# LCD_boad.net
KiCad netlist of a schematic drawn in EAGLE
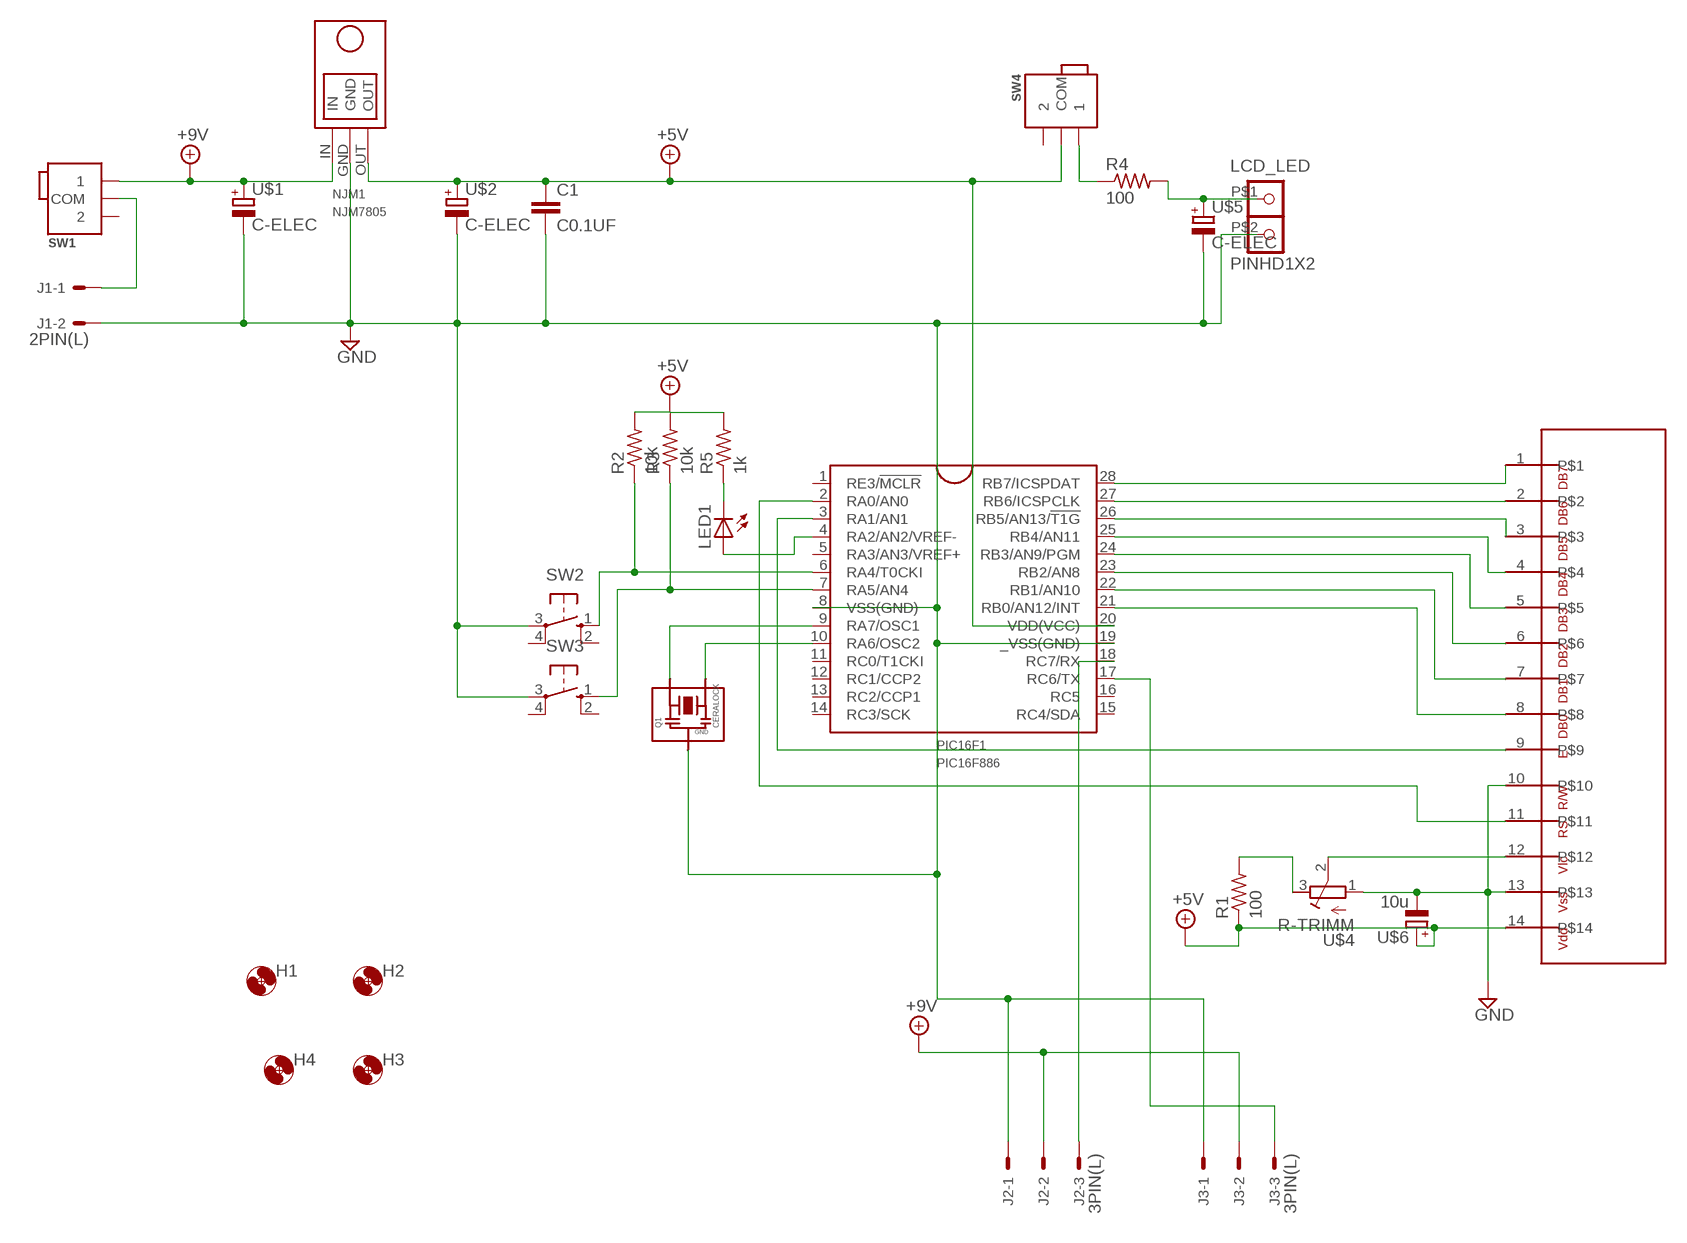
[diagram p0: schematic, sheet 1]

(export (version "E")
  (design (tool "Eeschema 10.0.6"))
  (components
    (comp (ref "C1")
      (value "C0.1UF")
      (footprint "eagle-import:C0.1UF")
      (libsource (lib "eagle-import") (part "C0.1UF"))
    )
    (comp (ref "H1")
      (value "HOLE3.3M3BOLT")
      (footprint "eagle-import:HOLE3.3")
      (libsource (lib "eagle-import") (part "HOLE3.3M3BOLT"))
    )
    (comp (ref "H2")
      (value "HOLE3.3M3BOLT")
      (footprint "eagle-import:HOLE3.3")
      (libsource (lib "eagle-import") (part "HOLE3.3M3BOLT"))
    )
    (comp (ref "H3")
      (value "HOLE3.3M3BOLT")
      (footprint "eagle-import:HOLE3.3")
      (libsource (lib "eagle-import") (part "HOLE3.3M3BOLT"))
    )
    (comp (ref "H4")
      (value "HOLE3.3M3BOLT")
      (footprint "eagle-import:HOLE3.3")
      (libsource (lib "eagle-import") (part "HOLE3.3M3BOLT"))
    )
    (comp (ref "J1")
      (value "2PIN(L)")
      (footprint "eagle-import:2PL")
      (libsource (lib "eagle-import") (part "2PIN(L)"))
    )
    (comp (ref "J2")
      (value "3PIN(L)")
      (footprint "eagle-import:3PL")
      (libsource (lib "eagle-import") (part "3PIN(L)"))
    )
    (comp (ref "J3")
      (value "3PIN(L)")
      (footprint "eagle-import:3PL")
      (libsource (lib "eagle-import") (part "3PIN(L)"))
    )
    (comp (ref "LCD_LED")
      (value "PINHD1X2")
      (footprint "eagle-import:PINHD1X2")
      (libsource (lib "eagle-import") (part "PINHD1X2"))
    )
    (comp (ref "LED1")
      (value "LED")
      (footprint "eagle-import:LED5MM")
      (libsource (lib "eagle-import") (part "LED"))
    )
    (comp (ref "NJM1")
      (value "NJM7805")
      (footprint "eagle-import:NJM7805")
      (libsource (lib "eagle-import") (part "NJM7805"))
    )
    (comp (ref "PIC16F1")
      (value "PIC16F886")
      (footprint "eagle-import:DIL28-3")
      (libsource (lib "eagle-import") (part "PIC16F886"))
    )
    (comp (ref "Q1")
      (value "CERALOCK")
      (footprint "eagle-import:CERALOCK")
      (libsource (lib "eagle-import") (part "CERALOCK"))
    )
    (comp (ref "R1")
      (value "100")
      (footprint "eagle-import:0207_10")
      (libsource (lib "eagle-import") (part "R-"))
    )
    (comp (ref "R2")
      (value "10k")
      (footprint "eagle-import:0207_10")
      (libsource (lib "eagle-import") (part "R-"))
    )
    (comp (ref "R3")
      (value "10k")
      (footprint "eagle-import:0207_10")
      (libsource (lib "eagle-import") (part "R-"))
    )
    (comp (ref "R4")
      (value "100")
      (footprint "eagle-import:0207_10")
      (libsource (lib "eagle-import") (part "R-"))
    )
    (comp (ref "R5")
      (value "1k")
      (footprint "eagle-import:0207_10")
      (libsource (lib "eagle-import") (part "R-"))
    )
    (comp (ref "SW1")
      (value "SWITCH_MININORMAL")
      (footprint "eagle-import:SWITCH_MINI")
      (libsource (lib "eagle-import") (part "SWITCH_MININORMAL"))
    )
    (comp (ref "SW2")
      (value "TACTSW")
      (footprint "eagle-import:TACT")
      (libsource (lib "eagle-import") (part "TACTSW"))
    )
    (comp (ref "SW3")
      (value "TACTSW")
      (footprint "eagle-import:TACT")
      (libsource (lib "eagle-import") (part "TACTSW"))
    )
    (comp (ref "SW4")
      (value "SWITCH_MININORMAL")
      (footprint "eagle-import:SWITCH_MINI")
      (libsource (lib "eagle-import") (part "SWITCH_MININORMAL"))
    )
    (comp (ref "U$1")
      (value "C-ELEC")
      (footprint "eagle-import:C-6MM")
      (libsource (lib "eagle-import") (part "C-ELEC"))
    )
    (comp (ref "U$2")
      (value "C-ELEC")
      (footprint "eagle-import:C-6MM")
      (libsource (lib "eagle-import") (part "C-ELEC"))
    )
    (comp (ref "U$3")
      (value "L1672D1JOOO")
      (footprint "eagle-import:Ｌ１６７２Ｄ１Ｊ０００")
      (libsource (lib "eagle-import") (part "L1672D1JOOO"))
    )
    (comp (ref "U$4")
      (value "R-TRIMM")
      (footprint "eagle-import:R-TRIMM")
      (libsource (lib "eagle-import") (part "R-TRIMM"))
    )
    (comp (ref "U$5")
      (value "C-ELEC")
      (footprint "eagle-import:C-6MM")
      (libsource (lib "eagle-import") (part "C-ELEC"))
    )
    (comp (ref "U$6")
      (value "10u")
      (footprint "eagle-import:C-6MM")
      (libsource (lib "eagle-import") (part "C-ELEC"))
    )
  )
  (nets
    (net (code "1") (name "+5V") (class "Default")
      (node (ref "C1") (pin "1") (pinfunction "1_1") (pintype "passive"))
      (node (ref "NJM1") (pin "OUT") (pinfunction "OUT_OUT") (pintype "bidirectional"))
      (node (ref "PIC16F1") (pin "20") (pinfunction "VDD(VCC)_20") (pintype "power_in"))
      (node (ref "R1") (pin "1") (pinfunction "1_1") (pintype "passive"))
      (node (ref "R2") (pin "2") (pinfunction "2_2") (pintype "passive"))
      (node (ref "R3") (pin "2") (pinfunction "2_2") (pintype "passive"))
      (node (ref "R5") (pin "2") (pinfunction "2_2") (pintype "passive"))
      (node (ref "SW4") (pin "COM") (pinfunction "COM_COM") (pintype "passive"))
      (node (ref "U$2") (pin "+") (pinfunction "+_+") (pintype "passive"))
      (node (ref "U$3") (pin "14") (pinfunction "P$14_14") (pintype "bidirectional"))
      (node (ref "U$6") (pin "+") (pinfunction "+_+") (pintype "passive"))
    )
    (net (code "2") (name "+9V") (class "Default")
      (node (ref "J2") (pin "2") (pinfunction "S_2") (pintype "passive"))
      (node (ref "J3") (pin "2") (pinfunction "S_2") (pintype "passive"))
      (node (ref "NJM1") (pin "IN") (pinfunction "IN_IN") (pintype "bidirectional"))
      (node (ref "SW1") (pin "1") (pinfunction "1_1") (pintype "passive"))
      (node (ref "U$1") (pin "+") (pinfunction "+_+") (pintype "passive"))
    )
    (net (code "3") (name "GND") (class "Default")
      (node (ref "C1") (pin "2") (pinfunction "2_2") (pintype "passive"))
      (node (ref "J1") (pin "2") (pinfunction "S_2") (pintype "passive"))
      (node (ref "J2") (pin "1") (pinfunction "S_1") (pintype "passive"))
      (node (ref "J3") (pin "1") (pinfunction "S_1") (pintype "passive"))
      (node (ref "LCD_LED") (pin "P$2") (pinfunction "3_P$2") (pintype "passive"))
      (node (ref "NJM1") (pin "GND") (pinfunction "GND_GND") (pintype "bidirectional"))
      (node (ref "PIC16F1") (pin "19") (pinfunction "_VSS(GND)_19") (pintype "power_in"))
      (node (ref "PIC16F1") (pin "8") (pinfunction "VSS(GND)_8") (pintype "power_in"))
      (node (ref "Q1") (pin "P$2") (pinfunction "P$2_P$2") (pintype "passive"))
      (node (ref "SW2") (pin "3") (pinfunction "P_3") (pintype "passive"))
      (node (ref "SW3") (pin "3") (pinfunction "P_3") (pintype "passive"))
      (node (ref "U$1") (pin "-") (pinfunction "-_-") (pintype "passive"))
      (node (ref "U$2") (pin "-") (pinfunction "-_-") (pintype "passive"))
      (node (ref "U$3") (pin "10") (pinfunction "P$10_10") (pintype "bidirectional"))
      (node (ref "U$3") (pin "13") (pinfunction "P$13_13") (pintype "bidirectional"))
      (node (ref "U$4") (pin "1") (pinfunction "1_1") (pintype "passive"))
      (node (ref "U$5") (pin "-") (pinfunction "-_-") (pintype "passive"))
      (node (ref "U$6") (pin "-") (pinfunction "-_-") (pintype "passive"))
    )
    (net (code "4") (name "Net-(J1A-S)") (class "Default")
      (node (ref "J1") (pin "1") (pinfunction "S_1") (pintype "passive"))
      (node (ref "SW1") (pin "COM") (pinfunction "COM_COM") (pintype "passive"))
    )
    (net (code "5") (name "Net-(J2C-S)") (class "Default")
      (node (ref "J2") (pin "3") (pinfunction "S_3") (pintype "passive"))
      (node (ref "PIC16F1") (pin "18") (pinfunction "RC7/RX_18") (pintype "bidirectional"))
    )
    (net (code "6") (name "Net-(J3C-S)") (class "Default")
      (node (ref "J3") (pin "3") (pinfunction "S_3") (pintype "passive"))
      (node (ref "PIC16F1") (pin "17") (pinfunction "RC6/TX_17") (pintype "bidirectional"))
    )
    (net (code "7") (name "Net-(LCD_LED-4)") (class "Default")
      (node (ref "LCD_LED") (pin "P$1") (pinfunction "4_P$1") (pintype "passive"))
      (node (ref "R4") (pin "2") (pinfunction "2_2") (pintype "passive"))
      (node (ref "U$5") (pin "+") (pinfunction "+_+") (pintype "passive"))
    )
    (net (code "8") (name "Net-(LED1-C)") (class "Default")
      (node (ref "LED1") (pin "K") (pinfunction "C_K") (pintype "passive"))
      (node (ref "R5") (pin "1") (pinfunction "1_1") (pintype "passive"))
    )
    (net (code "9") (name "Net-(PIC16F1-RA0{slash}AN0)") (class "Default")
      (node (ref "PIC16F1") (pin "2") (pinfunction "RA0/AN0_2") (pintype "bidirectional"))
      (node (ref "U$3") (pin "11") (pinfunction "P$11_11") (pintype "bidirectional"))
    )
    (net (code "10") (name "Net-(PIC16F1-RA1{slash}AN1)") (class "Default")
      (node (ref "PIC16F1") (pin "3") (pinfunction "RA1/AN1_3") (pintype "bidirectional"))
      (node (ref "U$3") (pin "9") (pinfunction "P$9_9") (pintype "bidirectional"))
    )
    (net (code "11") (name "Net-(PIC16F1-RA2{slash}AN2{slash}VREF-)") (class "Default")
      (node (ref "LED1") (pin "A") (pinfunction "A_A") (pintype "passive"))
      (node (ref "PIC16F1") (pin "4") (pinfunction "RA2/AN2/VREF-_4") (pintype "bidirectional"))
    )
    (net (code "12") (name "Net-(PIC16F1-RA4{slash}T0CKI)") (class "Default")
      (node (ref "PIC16F1") (pin "6") (pinfunction "RA4/T0CKI_6") (pintype "bidirectional"))
      (node (ref "R2") (pin "1") (pinfunction "1_1") (pintype "passive"))
      (node (ref "SW2") (pin "1") (pinfunction "S_1") (pintype "passive"))
    )
    (net (code "13") (name "Net-(PIC16F1-RA5{slash}AN4)") (class "Default")
      (node (ref "PIC16F1") (pin "7") (pinfunction "RA5/AN4_7") (pintype "bidirectional"))
      (node (ref "R3") (pin "1") (pinfunction "1_1") (pintype "passive"))
      (node (ref "SW3") (pin "1") (pinfunction "S_1") (pintype "passive"))
    )
    (net (code "14") (name "Net-(PIC16F1-RA6{slash}OSC2)") (class "Default")
      (node (ref "PIC16F1") (pin "10") (pinfunction "RA6/OSC2_10") (pintype "bidirectional"))
      (node (ref "Q1") (pin "P$3") (pinfunction "P$3_P$3") (pintype "passive"))
    )
    (net (code "15") (name "Net-(PIC16F1-RA7{slash}OSC1)") (class "Default")
      (node (ref "PIC16F1") (pin "9") (pinfunction "RA7/OSC1_9") (pintype "bidirectional"))
      (node (ref "Q1") (pin "P$1") (pinfunction "P$1_P$1") (pintype "passive"))
    )
    (net (code "16") (name "Net-(PIC16F1-RB0{slash}AN12{slash}INT)") (class "Default")
      (node (ref "PIC16F1") (pin "21") (pinfunction "RB0/AN12/INT_21") (pintype "bidirectional"))
      (node (ref "U$3") (pin "8") (pinfunction "P$8_8") (pintype "bidirectional"))
    )
    (net (code "17") (name "Net-(PIC16F1-RB1{slash}AN10)") (class "Default")
      (node (ref "PIC16F1") (pin "22") (pinfunction "RB1/AN10_22") (pintype "bidirectional"))
      (node (ref "U$3") (pin "7") (pinfunction "P$7_7") (pintype "bidirectional"))
    )
    (net (code "18") (name "Net-(PIC16F1-RB2{slash}AN8)") (class "Default")
      (node (ref "PIC16F1") (pin "23") (pinfunction "RB2/AN8_23") (pintype "bidirectional"))
      (node (ref "U$3") (pin "6") (pinfunction "P$6_6") (pintype "bidirectional"))
    )
    (net (code "19") (name "Net-(PIC16F1-RB3{slash}AN9{slash}PGM)") (class "Default")
      (node (ref "PIC16F1") (pin "24") (pinfunction "RB3/AN9/PGM_24") (pintype "bidirectional"))
      (node (ref "U$3") (pin "5") (pinfunction "P$5_5") (pintype "bidirectional"))
    )
    (net (code "20") (name "Net-(PIC16F1-RB4{slash}AN11)") (class "Default")
      (node (ref "PIC16F1") (pin "25") (pinfunction "RB4/AN11_25") (pintype "bidirectional"))
      (node (ref "U$3") (pin "4") (pinfunction "P$4_4") (pintype "bidirectional"))
    )
    (net (code "21") (name "Net-(PIC16F1-RB5{slash}AN13{slash}~{T1G})") (class "Default")
      (node (ref "PIC16F1") (pin "26") (pinfunction "RB5/AN13/~{T1G}_26") (pintype "bidirectional"))
      (node (ref "U$3") (pin "3") (pinfunction "P$3_3") (pintype "bidirectional"))
    )
    (net (code "22") (name "Net-(PIC16F1-RB6{slash}ICSPCLK)") (class "Default")
      (node (ref "PIC16F1") (pin "27") (pinfunction "RB6/ICSPCLK_27") (pintype "bidirectional"))
      (node (ref "U$3") (pin "2") (pinfunction "P$2_2") (pintype "bidirectional"))
    )
    (net (code "23") (name "Net-(PIC16F1-RB7{slash}ICSPDAT)") (class "Default")
      (node (ref "PIC16F1") (pin "28") (pinfunction "RB7/ICSPDAT_28") (pintype "bidirectional"))
      (node (ref "U$3") (pin "1") (pinfunction "P$1_1") (pintype "bidirectional"))
    )
    (net (code "24") (name "Net-(R1-Pad2)") (class "Default")
      (node (ref "R1") (pin "2") (pinfunction "2_2") (pintype "passive"))
      (node (ref "U$4") (pin "3") (pinfunction "3_3") (pintype "passive"))
    )
    (net (code "25") (name "Net-(R4-Pad1)") (class "Default")
      (node (ref "R4") (pin "1") (pinfunction "1_1") (pintype "passive"))
      (node (ref "SW4") (pin "1") (pinfunction "1_1") (pintype "passive"))
    )
    (net (code "26") (name "Net-(U$3-P$12)") (class "Default")
      (node (ref "U$3") (pin "12") (pinfunction "P$12_12") (pintype "bidirectional"))
      (node (ref "U$4") (pin "2") (pinfunction "2_2") (pintype "passive"))
    )
    (net (code "27") (name "unconnected-(PIC16F1-RA3{slash}AN3{slash}VREF+-Pad5)") (class "Default")
      (node (ref "PIC16F1") (pin "5") (pinfunction "RA3/AN3/VREF+_5") (pintype "bidirectional"))
    )
    (net (code "28") (name "unconnected-(PIC16F1-RC0{slash}T1CKI-Pad11)") (class "Default")
      (node (ref "PIC16F1") (pin "11") (pinfunction "RC0/T1CKI_11") (pintype "bidirectional"))
    )
    (net (code "29") (name "unconnected-(PIC16F1-RC1{slash}CCP2-Pad12)") (class "Default")
      (node (ref "PIC16F1") (pin "12") (pinfunction "RC1/CCP2_12") (pintype "bidirectional"))
    )
    (net (code "30") (name "unconnected-(PIC16F1-RC2{slash}CCP1-Pad13)") (class "Default")
      (node (ref "PIC16F1") (pin "13") (pinfunction "RC2/CCP1_13") (pintype "bidirectional"))
    )
    (net (code "31") (name "unconnected-(PIC16F1-RC3{slash}SCK-Pad14)") (class "Default")
      (node (ref "PIC16F1") (pin "14") (pinfunction "RC3/SCK_14") (pintype "bidirectional"))
    )
    (net (code "32") (name "unconnected-(PIC16F1-RC4{slash}SDA-Pad15)") (class "Default")
      (node (ref "PIC16F1") (pin "15") (pinfunction "RC4/SDA_15") (pintype "bidirectional"))
    )
    (net (code "33") (name "unconnected-(PIC16F1-RC5-Pad16)") (class "Default")
      (node (ref "PIC16F1") (pin "16") (pinfunction "RC5_16") (pintype "bidirectional"))
    )
    (net (code "34") (name "unconnected-(PIC16F1-RE3{slash}~{MCLR}-Pad1)") (class "Default")
      (node (ref "PIC16F1") (pin "1") (pinfunction "RE3/~{MCLR}_1") (pintype "bidirectional"))
    )
    (net (code "35") (name "unconnected-(SW1-Pad2)") (class "Default")
      (node (ref "SW1") (pin "2") (pinfunction "2_2") (pintype "no_connect"))
    )
    (net (code "36") (name "unconnected-(SW2-P1-Pad4)") (class "Default")
      (node (ref "SW2") (pin "4") (pinfunction "P1_4") (pintype "passive"))
    )
    (net (code "37") (name "unconnected-(SW2-S1-Pad2)") (class "Default")
      (node (ref "SW2") (pin "2") (pinfunction "S1_2") (pintype "passive"))
    )
    (net (code "38") (name "unconnected-(SW3-P1-Pad4)") (class "Default")
      (node (ref "SW3") (pin "4") (pinfunction "P1_4") (pintype "passive"))
    )
    (net (code "39") (name "unconnected-(SW3-S1-Pad2)") (class "Default")
      (node (ref "SW3") (pin "2") (pinfunction "S1_2") (pintype "passive"))
    )
    (net (code "40") (name "unconnected-(SW4-Pad2)") (class "Default")
      (node (ref "SW4") (pin "2") (pinfunction "2_2") (pintype "no_connect"))
    )
  )
)
